# pontos_cegos_pth.net
KiCad netlist of a schematic drawn in EAGLE
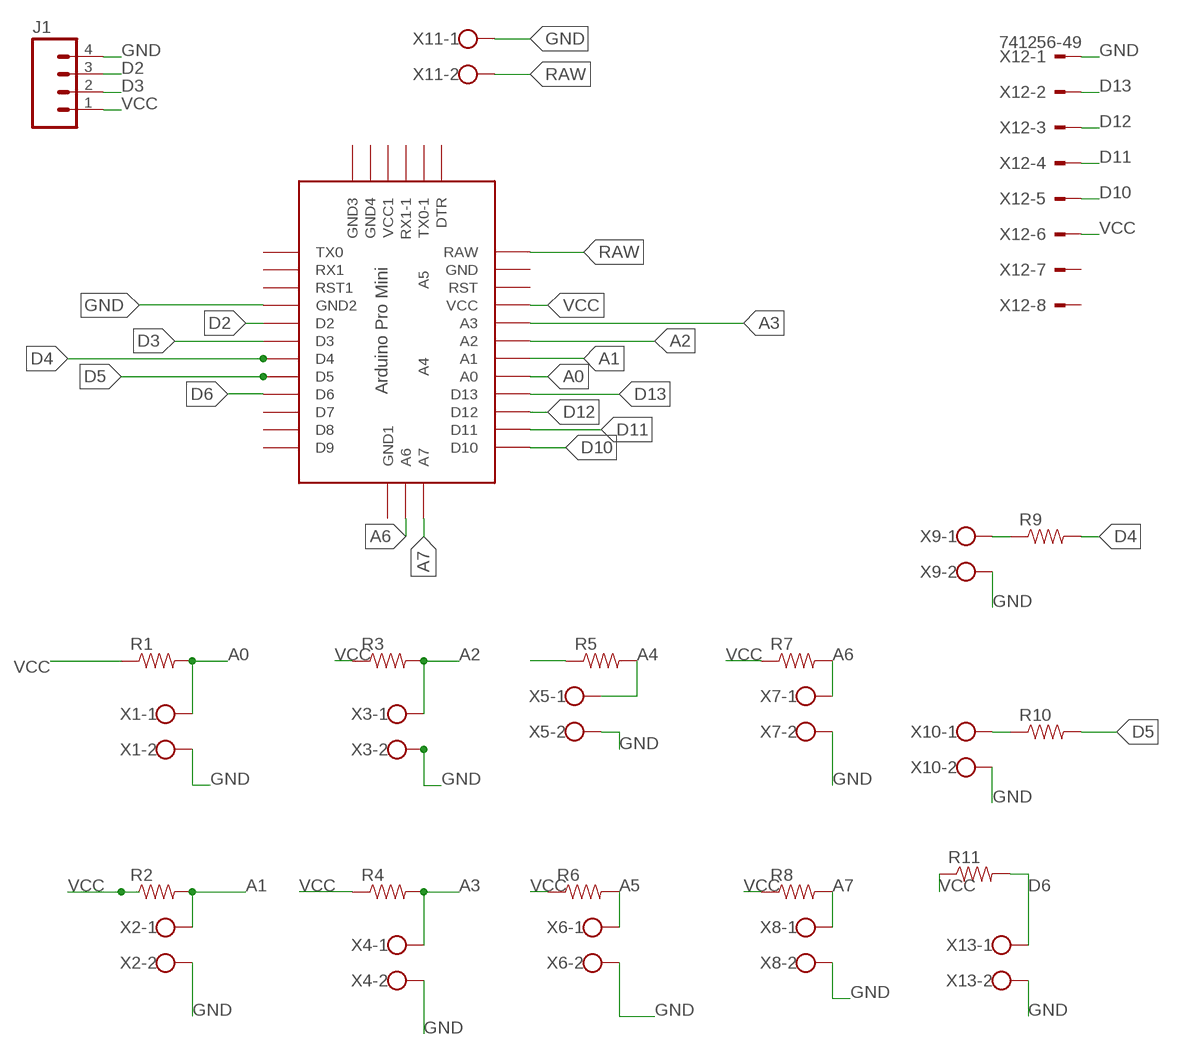
[diagram p0: schematic, sheet 1]

(export (version "E")
  (design (tool "Eeschema 10.0.6"))
  (components
    (comp (ref "J1")
      (value "M04LONGPADS")
      (footprint "eagle-import:1X04_LONGPADS")
      (libsource (lib "eagle-import") (part "M04LONGPADS"))
    )
    (comp (ref "R1")
      (value "RESISTORAXIAL-0.3")
      (footprint "eagle-import:AXIAL-0.3")
      (libsource (lib "eagle-import") (part "RESISTORAXIAL-0.3"))
    )
    (comp (ref "R2")
      (value "RESISTORAXIAL-0.3")
      (footprint "eagle-import:AXIAL-0.3")
      (libsource (lib "eagle-import") (part "RESISTORAXIAL-0.3"))
    )
    (comp (ref "R3")
      (value "RESISTORAXIAL-0.3")
      (footprint "eagle-import:AXIAL-0.3")
      (libsource (lib "eagle-import") (part "RESISTORAXIAL-0.3"))
    )
    (comp (ref "R4")
      (value "RESISTORAXIAL-0.3")
      (footprint "eagle-import:AXIAL-0.3")
      (libsource (lib "eagle-import") (part "RESISTORAXIAL-0.3"))
    )
    (comp (ref "R5")
      (value "RESISTORAXIAL-0.3")
      (footprint "eagle-import:AXIAL-0.3")
      (libsource (lib "eagle-import") (part "RESISTORAXIAL-0.3"))
    )
    (comp (ref "R6")
      (value "RESISTORAXIAL-0.3")
      (footprint "eagle-import:AXIAL-0.3")
      (libsource (lib "eagle-import") (part "RESISTORAXIAL-0.3"))
    )
    (comp (ref "R7")
      (value "RESISTORAXIAL-0.3")
      (footprint "eagle-import:AXIAL-0.3")
      (libsource (lib "eagle-import") (part "RESISTORAXIAL-0.3"))
    )
    (comp (ref "R8")
      (value "RESISTORAXIAL-0.3")
      (footprint "eagle-import:AXIAL-0.3")
      (libsource (lib "eagle-import") (part "RESISTORAXIAL-0.3"))
    )
    (comp (ref "R9")
      (value "RESISTORAXIAL-0.3")
      (footprint "eagle-import:AXIAL-0.3")
      (libsource (lib "eagle-import") (part "RESISTORAXIAL-0.3"))
    )
    (comp (ref "R10")
      (value "RESISTORAXIAL-0.3")
      (footprint "eagle-import:AXIAL-0.3")
      (libsource (lib "eagle-import") (part "RESISTORAXIAL-0.3"))
    )
    (comp (ref "R11")
      (value "RESISTORAXIAL-0.3")
      (footprint "eagle-import:AXIAL-0.3")
      (libsource (lib "eagle-import") (part "RESISTORAXIAL-0.3"))
    )
    (comp (ref "U$1")
      (value "ABK-PRO-MINI")
      (footprint "eagle-import:ABK-PRO-MINI")
      (libsource (lib "eagle-import") (part "ABK-PRO-MINI"))
    )
    (comp (ref "X1")
      (value "W237-102")
      (footprint "eagle-import:W237-102")
      (fields (field (name "MPN") "237-102"))
      (libsource (lib "eagle-import") (part "W237-102"))
    )
    (comp (ref "X2")
      (value "W237-102")
      (footprint "eagle-import:W237-102")
      (fields (field (name "MPN") "237-102"))
      (libsource (lib "eagle-import") (part "W237-102"))
    )
    (comp (ref "X3")
      (value "W237-102")
      (footprint "eagle-import:W237-102")
      (fields (field (name "MPN") "237-102"))
      (libsource (lib "eagle-import") (part "W237-102"))
    )
    (comp (ref "X4")
      (value "W237-102")
      (footprint "eagle-import:W237-102")
      (fields (field (name "MPN") "237-102"))
      (libsource (lib "eagle-import") (part "W237-102"))
    )
    (comp (ref "X5")
      (value "W237-102")
      (footprint "eagle-import:W237-102")
      (fields (field (name "MPN") "237-102"))
      (libsource (lib "eagle-import") (part "W237-102"))
    )
    (comp (ref "X6")
      (value "W237-102")
      (footprint "eagle-import:W237-102")
      (fields (field (name "MPN") "237-102"))
      (libsource (lib "eagle-import") (part "W237-102"))
    )
    (comp (ref "X7")
      (value "W237-102")
      (footprint "eagle-import:W237-102")
      (fields (field (name "MPN") "237-102"))
      (libsource (lib "eagle-import") (part "W237-102"))
    )
    (comp (ref "X8")
      (value "W237-102")
      (footprint "eagle-import:W237-102")
      (fields (field (name "MPN") "237-102"))
      (libsource (lib "eagle-import") (part "W237-102"))
    )
    (comp (ref "X9")
      (value "W237-102")
      (footprint "eagle-import:W237-102")
      (fields (field (name "MPN") "237-102"))
      (libsource (lib "eagle-import") (part "W237-102"))
    )
    (comp (ref "X10")
      (value "W237-102")
      (footprint "eagle-import:W237-102")
      (fields (field (name "MPN") "237-102"))
      (libsource (lib "eagle-import") (part "W237-102"))
    )
    (comp (ref "X11")
      (value "W237-102")
      (footprint "eagle-import:W237-102")
      (fields (field (name "MPN") "237-102"))
      (libsource (lib "eagle-import") (part "W237-102"))
    )
    (comp (ref "X12")
      (value "741256-49")
      (footprint "eagle-import:741256-49")
      (libsource (lib "eagle-import") (part "741256-49"))
    )
    (comp (ref "X13")
      (value "W237-102")
      (footprint "eagle-import:W237-102")
      (fields (field (name "MPN") "237-102"))
      (libsource (lib "eagle-import") (part "W237-102"))
    )
  )
  (nets
    (net (code "1") (name "/A4") (class "Default")
      (node (ref "R5") (pin "P$2") (pinfunction "2_P$2") (pintype "passive"))
      (node (ref "X5") (pin "1") (pinfunction "KL_1") (pintype "passive"))
    )
    (net (code "2") (name "/A5") (class "Default")
      (node (ref "R6") (pin "P$2") (pinfunction "2_P$2") (pintype "passive"))
      (node (ref "X6") (pin "1") (pinfunction "KL_1") (pintype "passive"))
    )
    (net (code "3") (name "A0") (class "Default")
      (node (ref "R1") (pin "P$2") (pinfunction "2_P$2") (pintype "passive"))
      (node (ref "U$1") (pin "A0") (pinfunction "A0_A0") (pintype "bidirectional"))
      (node (ref "X1") (pin "1") (pinfunction "KL_1") (pintype "passive"))
    )
    (net (code "4") (name "A1") (class "Default")
      (node (ref "R2") (pin "P$2") (pinfunction "2_P$2") (pintype "passive"))
      (node (ref "U$1") (pin "A1") (pinfunction "A1_A1") (pintype "bidirectional"))
      (node (ref "X2") (pin "1") (pinfunction "KL_1") (pintype "passive"))
    )
    (net (code "5") (name "A2") (class "Default")
      (node (ref "R3") (pin "P$2") (pinfunction "2_P$2") (pintype "passive"))
      (node (ref "U$1") (pin "A2") (pinfunction "A2_A2") (pintype "bidirectional"))
      (node (ref "X3") (pin "1") (pinfunction "KL_1") (pintype "passive"))
    )
    (net (code "6") (name "A3") (class "Default")
      (node (ref "R4") (pin "P$2") (pinfunction "2_P$2") (pintype "passive"))
      (node (ref "U$1") (pin "A3") (pinfunction "A3_A3") (pintype "bidirectional"))
      (node (ref "X4") (pin "1") (pinfunction "KL_1") (pintype "passive"))
    )
    (net (code "7") (name "A6") (class "Default")
      (node (ref "R7") (pin "P$2") (pinfunction "2_P$2") (pintype "passive"))
      (node (ref "U$1") (pin "A6") (pinfunction "A6_A6") (pintype "bidirectional"))
      (node (ref "X7") (pin "1") (pinfunction "KL_1") (pintype "passive"))
    )
    (net (code "8") (name "A7") (class "Default")
      (node (ref "R8") (pin "P$2") (pinfunction "2_P$2") (pintype "passive"))
      (node (ref "U$1") (pin "A7") (pinfunction "A7_A7") (pintype "bidirectional"))
      (node (ref "X8") (pin "1") (pinfunction "KL_1") (pintype "passive"))
    )
    (net (code "9") (name "D2") (class "Default")
      (node (ref "J1") (pin "3") (pinfunction "3_3") (pintype "passive"))
      (node (ref "U$1") (pin "D2") (pinfunction "D2_D2") (pintype "bidirectional"))
    )
    (net (code "10") (name "D3") (class "Default")
      (node (ref "J1") (pin "2") (pinfunction "2_2") (pintype "passive"))
      (node (ref "U$1") (pin "D3") (pinfunction "D3_D3") (pintype "bidirectional"))
    )
    (net (code "11") (name "D4") (class "Default")
      (node (ref "R9") (pin "P$2") (pinfunction "2_P$2") (pintype "passive"))
      (node (ref "U$1") (pin "D4") (pinfunction "D4_D4") (pintype "bidirectional"))
    )
    (net (code "12") (name "D5") (class "Default")
      (node (ref "R10") (pin "P$2") (pinfunction "2_P$2") (pintype "passive"))
      (node (ref "U$1") (pin "D5") (pinfunction "D5_D5") (pintype "bidirectional"))
    )
    (net (code "13") (name "D6") (class "Default")
      (node (ref "R11") (pin "P$2") (pinfunction "2_P$2") (pintype "passive"))
      (node (ref "U$1") (pin "D6") (pinfunction "D6_D6") (pintype "bidirectional"))
      (node (ref "X13") (pin "1") (pinfunction "KL_1") (pintype "passive"))
    )
    (net (code "14") (name "D10") (class "Default")
      (node (ref "U$1") (pin "D10") (pinfunction "D10_D10") (pintype "bidirectional"))
      (node (ref "X12") (pin "5") (pinfunction "KL_5") (pintype "passive"))
    )
    (net (code "15") (name "D11") (class "Default")
      (node (ref "U$1") (pin "D11") (pinfunction "D11_D11") (pintype "bidirectional"))
      (node (ref "X12") (pin "4") (pinfunction "KL_4") (pintype "passive"))
    )
    (net (code "16") (name "D12") (class "Default")
      (node (ref "U$1") (pin "D12") (pinfunction "D12_D12") (pintype "bidirectional"))
      (node (ref "X12") (pin "3") (pinfunction "KL_3") (pintype "passive"))
    )
    (net (code "17") (name "D13") (class "Default")
      (node (ref "U$1") (pin "D13") (pinfunction "D13_D13") (pintype "bidirectional"))
      (node (ref "X12") (pin "2") (pinfunction "KL_2") (pintype "passive"))
    )
    (net (code "18") (name "GND") (class "Default")
      (node (ref "J1") (pin "4") (pinfunction "4_4") (pintype "passive"))
      (node (ref "U$1") (pin "GND1") (pinfunction "GND2_GND1") (pintype "bidirectional"))
      (node (ref "X1") (pin "2") (pinfunction "KL_2") (pintype "passive"))
      (node (ref "X10") (pin "2") (pinfunction "KL_2") (pintype "passive"))
      (node (ref "X11") (pin "1") (pinfunction "KL_1") (pintype "passive"))
      (node (ref "X12") (pin "1") (pinfunction "KL_1") (pintype "passive"))
      (node (ref "X13") (pin "2") (pinfunction "KL_2") (pintype "passive"))
      (node (ref "X2") (pin "2") (pinfunction "KL_2") (pintype "passive"))
      (node (ref "X3") (pin "2") (pinfunction "KL_2") (pintype "passive"))
      (node (ref "X4") (pin "2") (pinfunction "KL_2") (pintype "passive"))
      (node (ref "X5") (pin "2") (pinfunction "KL_2") (pintype "passive"))
      (node (ref "X6") (pin "2") (pinfunction "KL_2") (pintype "passive"))
      (node (ref "X7") (pin "2") (pinfunction "KL_2") (pintype "passive"))
      (node (ref "X8") (pin "2") (pinfunction "KL_2") (pintype "passive"))
      (node (ref "X9") (pin "2") (pinfunction "KL_2") (pintype "passive"))
    )
    (net (code "19") (name "Net-(R9-1)") (class "Default")
      (node (ref "R9") (pin "P$1") (pinfunction "1_P$1") (pintype "passive"))
      (node (ref "X9") (pin "1") (pinfunction "KL_1") (pintype "passive"))
    )
    (net (code "20") (name "Net-(R10-1)") (class "Default")
      (node (ref "R10") (pin "P$1") (pinfunction "1_P$1") (pintype "passive"))
      (node (ref "X10") (pin "1") (pinfunction "KL_1") (pintype "passive"))
    )
    (net (code "21") (name "RAW") (class "Default")
      (node (ref "U$1") (pin "RAW") (pinfunction "RAW_RAW") (pintype "bidirectional"))
      (node (ref "X11") (pin "2") (pinfunction "KL_2") (pintype "passive"))
    )
    (net (code "22") (name "VCC") (class "Default")
      (node (ref "J1") (pin "1") (pinfunction "1_1") (pintype "passive"))
      (node (ref "R1") (pin "P$1") (pinfunction "1_P$1") (pintype "passive"))
      (node (ref "R11") (pin "P$1") (pinfunction "1_P$1") (pintype "passive"))
      (node (ref "R2") (pin "P$1") (pinfunction "1_P$1") (pintype "passive"))
      (node (ref "R3") (pin "P$1") (pinfunction "1_P$1") (pintype "passive"))
      (node (ref "R4") (pin "P$1") (pinfunction "1_P$1") (pintype "passive"))
      (node (ref "R5") (pin "P$1") (pinfunction "1_P$1") (pintype "passive"))
      (node (ref "R6") (pin "P$1") (pinfunction "1_P$1") (pintype "passive"))
      (node (ref "R7") (pin "P$1") (pinfunction "1_P$1") (pintype "passive"))
      (node (ref "R8") (pin "P$1") (pinfunction "1_P$1") (pintype "passive"))
      (node (ref "U$1") (pin "VCC") (pinfunction "VCC_VCC") (pintype "bidirectional"))
      (node (ref "X12") (pin "6") (pinfunction "KL_6") (pintype "passive"))
    )
    (net (code "23") (name "unconnected-(U$1-GND1-PadGND4)") (class "Default")
      (node (ref "U$1") (pin "GND4") (pinfunction "GND1_GND4") (pintype "bidirectional"))
    )
    (net (code "24") (name "unconnected-(U$1-GND3-PadGND2)") (class "Default")
      (node (ref "U$1") (pin "GND2") (pinfunction "GND3_GND2") (pintype "bidirectional"))
    )
    (net (code "25") (name "unconnected-(U$1-GND4-PadGND3)") (class "Default")
      (node (ref "U$1") (pin "GND3") (pinfunction "GND4_GND3") (pintype "bidirectional"))
    )
    (net (code "26") (name "unconnected-(U$1-PadA4)") (class "Default")
      (node (ref "U$1") (pin "A4") (pinfunction "A4_A4") (pintype "bidirectional"))
    )
    (net (code "27") (name "unconnected-(U$1-PadA5)") (class "Default")
      (node (ref "U$1") (pin "A5") (pinfunction "A5_A5") (pintype "bidirectional"))
    )
    (net (code "28") (name "unconnected-(U$1-PadD7)") (class "Default")
      (node (ref "U$1") (pin "D7") (pinfunction "D7_D7") (pintype "bidirectional"))
    )
    (net (code "29") (name "unconnected-(U$1-PadD8)") (class "Default")
      (node (ref "U$1") (pin "D8") (pinfunction "D8_D8") (pintype "bidirectional"))
    )
    (net (code "30") (name "unconnected-(U$1-PadD9)") (class "Default")
      (node (ref "U$1") (pin "D9") (pinfunction "D9_D9") (pintype "bidirectional"))
    )
    (net (code "31") (name "unconnected-(U$1-PadDTR)") (class "Default")
      (node (ref "U$1") (pin "DTR") (pinfunction "DTR_DTR") (pintype "bidirectional"))
    )
    (net (code "32") (name "unconnected-(U$1-PadGND)") (class "Default")
      (node (ref "U$1") (pin "GND") (pinfunction "GND_GND") (pintype "bidirectional"))
    )
    (net (code "33") (name "unconnected-(U$1-PadRST)") (class "Default")
      (node (ref "U$1") (pin "RST") (pinfunction "RST_RST") (pintype "bidirectional"))
    )
    (net (code "34") (name "unconnected-(U$1-PadRST1)") (class "Default")
      (node (ref "U$1") (pin "RST1") (pinfunction "RST1_RST1") (pintype "bidirectional"))
    )
    (net (code "35") (name "unconnected-(U$1-PadRX1)") (class "Default")
      (node (ref "U$1") (pin "RX1") (pinfunction "RX1_RX1") (pintype "bidirectional"))
    )
    (net (code "36") (name "unconnected-(U$1-PadRX1-1)") (class "Default")
      (node (ref "U$1") (pin "RX1-1") (pinfunction "RX1-1_RX1-1") (pintype "bidirectional"))
    )
    (net (code "37") (name "unconnected-(U$1-PadTX0)") (class "Default")
      (node (ref "U$1") (pin "TX0") (pinfunction "TX0_TX0") (pintype "bidirectional"))
    )
    (net (code "38") (name "unconnected-(U$1-PadTX0-1)") (class "Default")
      (node (ref "U$1") (pin "TX0-1") (pinfunction "TX0-1_TX0-1") (pintype "bidirectional"))
    )
    (net (code "39") (name "unconnected-(U$1-PadVCC1)") (class "Default")
      (node (ref "U$1") (pin "VCC1") (pinfunction "VCC1_VCC1") (pintype "bidirectional"))
    )
    (net (code "40") (name "unconnected-(X12G-KL-Pad7)") (class "Default")
      (node (ref "X12") (pin "7") (pinfunction "KL_7") (pintype "passive"))
    )
    (net (code "41") (name "unconnected-(X12H-KL-Pad8)") (class "Default")
      (node (ref "X12") (pin "8") (pinfunction "KL_8") (pintype "passive"))
    )
  )
)
